# PowerB.net
KiCad netlist of a schematic drawn in Altium Designer
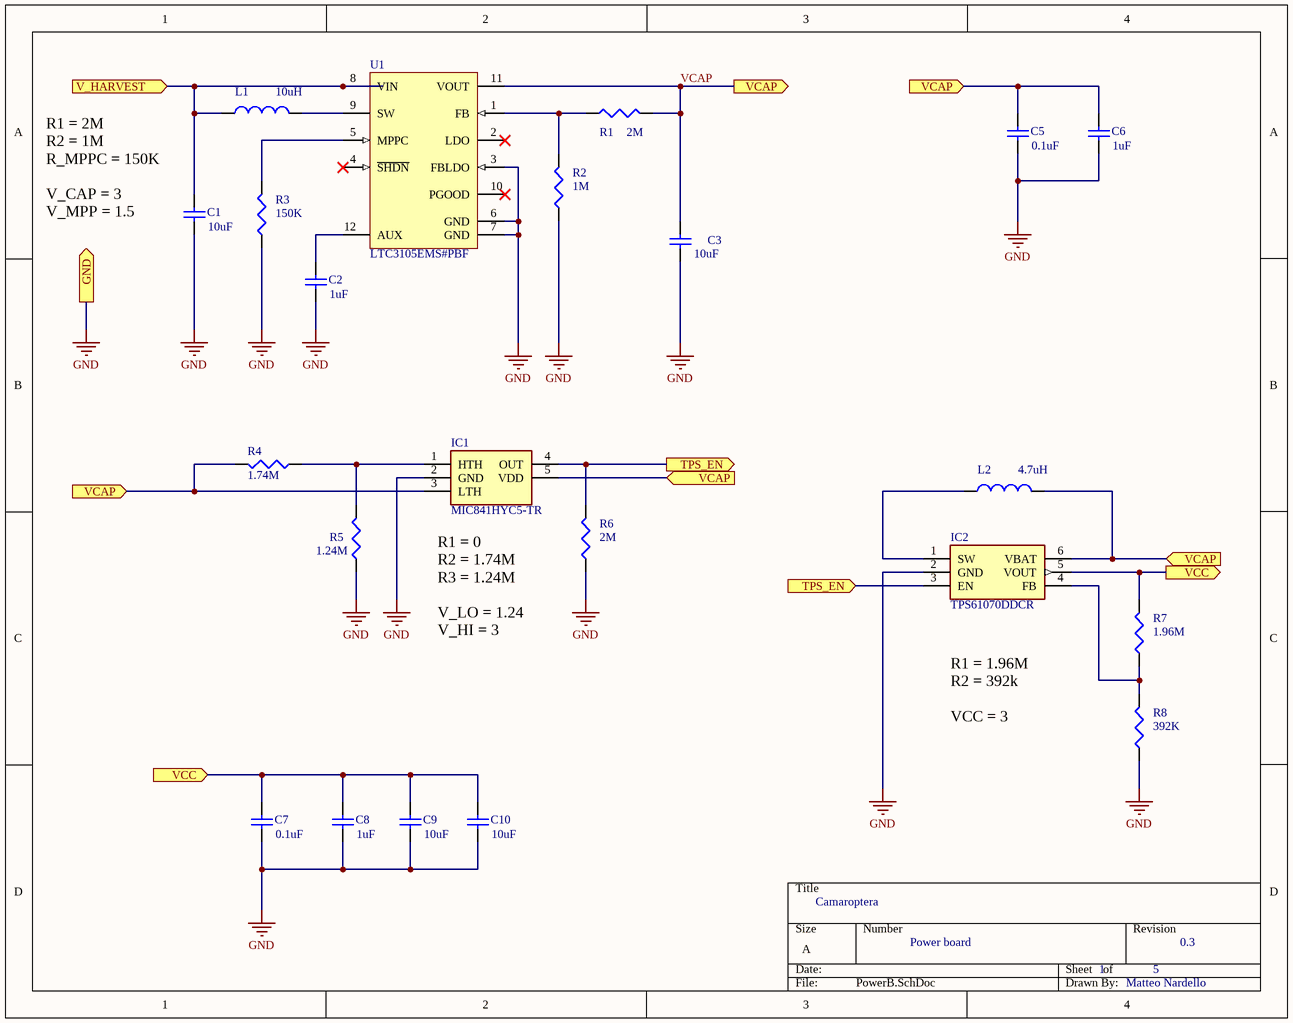
[diagram p0: PowerB.SchDoc]

(export (version "E")
  (design (tool "Eeschema 10.0.6"))
  (components
    (comp (ref "C1")
      (value "10uF")
      (footprint "1608[0603]")
      (description "CAP CER 6.3V X5R/X7R 0603")
      (fields (field (name "Comment") "Cap") (field (name "PUBLISHER") "Altium Limited"))
      (libsource (lib "Miscellaneous Devices") (part "Cap"))
    )
    (comp (ref "C2")
      (value "1uF")
      (footprint "1608[0603]")
      (description "CAP CER 6.3V X5R/X7R 0603")
      (fields (field (name "Comment") "Cap") (field (name "PUBLISHER") "Altium Limited"))
      (libsource (lib "Miscellaneous Devices") (part "Cap"))
    )
    (comp (ref "C3")
      (value "10uF")
      (footprint "1608[0603]")
      (description "CAP CER 6.3V X5R/X7R 0603")
      (fields (field (name "Comment") "Cap") (field (name "PUBLISHER") "Altium Limited"))
      (libsource (lib "Miscellaneous Devices") (part "Cap"))
    )
    (comp (ref "C5")
      (value "0.1uF")
      (footprint "1608[0603]")
      (description "CAP CER 6.3V X5R/X7R 0603")
      (fields (field (name "Comment") "Cap") (field (name "PUBLISHER") "Altium Limited"))
      (libsource (lib "Miscellaneous Devices") (part "Cap"))
    )
    (comp (ref "C6")
      (value "1uF")
      (footprint "1608[0603]")
      (description "CAP CER 6.3V X5R/X7R 0603")
      (fields (field (name "Comment") "Cap") (field (name "PUBLISHER") "Altium Limited"))
      (libsource (lib "Miscellaneous Devices") (part "Cap"))
    )
    (comp (ref "C7")
      (value "0.1uF")
      (footprint "1608[0603]")
      (description "CAP CER 6.3V X5R/X7R 0603")
      (fields (field (name "Comment") "Cap") (field (name "PUBLISHER") "Altium Limited"))
      (libsource (lib "Miscellaneous Devices") (part "Cap"))
    )
    (comp (ref "C8")
      (value "1uF")
      (footprint "1608[0603]")
      (description "CAP CER 6.3V X5R/X7R 0603")
      (fields (field (name "Comment") "Cap") (field (name "PUBLISHER") "Altium Limited"))
      (libsource (lib "Miscellaneous Devices") (part "Cap"))
    )
    (comp (ref "C9")
      (value "10uF")
      (footprint "1608[0603]")
      (description "CAP CER 6.3V X5R/X7R 0603")
      (fields (field (name "Comment") "Cap") (field (name "PUBLISHER") "Altium Limited"))
      (libsource (lib "Miscellaneous Devices") (part "Cap"))
    )
    (comp (ref "C10")
      (value "10uF")
      (footprint "1608[0603]")
      (description "CAP CER 6.3V X5R/X7R 0603")
      (fields (field (name "Comment") "Cap") (field (name "PUBLISHER") "Altium Limited"))
      (libsource (lib "Miscellaneous Devices") (part "Cap"))
    )
    (comp (ref "IC1")
      (value "MIC841HYC5-TR")
      (footprint "SamacSys:SOT65P210X110-5N")
      (description "Comparator with 1.25% Reference and Adjustable Hysteresis")
      (fields
        (field (name "MOUSER PART NUMBER") "998-MIC841HYC5TR")
        (field (name "RS PART NUMBER") "1654292")
      )
      (libsource (lib "*") (part "MIC841HYC5-TR"))
    )
    (comp (ref "IC2")
      (value "TPS61070DDCR")
      (footprint "SamacSys:SOT95P280X110-6N")
      (description "90% Efficient Synchronous Boost Converter With 600-mA Switch")
      (fields (field (name "MOUSER PART NUMBER") "595-TPS61070DDCR"))
      (libsource (lib "*") (part "TPS61070DDCR"))
    )
    (comp (ref "L1")
      (value "10uH")
      (footprint "C1210")
      (description "Inductor")
      (fields (field (name "PART") "CBC3225T100KR") (field (name "PUBLISHER") "Altium Limited"))
      (libsource (lib "Miscellaneous Devices") (part "Inductor"))
    )
    (comp (ref "L2")
      (value "4.7uH")
      (footprint "C1210")
      (description "Inductor")
      (fields (field (name "PART") "CBC3225T4R7MR") (field (name "PUBLISHER") "Altium Limited"))
      (libsource (lib "Miscellaneous Devices") (part "Inductor"))
    )
    (comp (ref "R1")
      (value "2M")
      (footprint "1608[0603]")
      (description "RES 1/10W 1% 0603 SMD")
      (fields (field (name "Comment") "Res3") (field (name "PUBLISHER") "Altium Limited"))
      (libsource (lib "Miscellaneous Devices") (part "Res3"))
    )
    (comp (ref "R2")
      (value "1M")
      (footprint "1608[0603]")
      (description "RES 1/10W 1% 0603 SMD")
      (fields (field (name "Comment") "Res3") (field (name "PUBLISHER") "Altium Limited"))
      (libsource (lib "Miscellaneous Devices") (part "Res3"))
    )
    (comp (ref "R3")
      (value "150K")
      (footprint "1608[0603]")
      (description "RES 1/10W 1% 0603 SMD")
      (fields (field (name "Comment") "Res3") (field (name "PUBLISHER") "Altium Limited"))
      (libsource (lib "Miscellaneous Devices") (part "Res3"))
    )
    (comp (ref "R4")
      (value "1.74M")
      (footprint "1608[0603]")
      (description "RES 1/10W 1% 0603 SMD")
      (fields (field (name "Comment") "Res3") (field (name "PUBLISHER") "Altium Limited"))
      (libsource (lib "Miscellaneous Devices") (part "Res3"))
    )
    (comp (ref "R5")
      (value "1.24M")
      (footprint "1608[0603]")
      (description "RES 1/10W 1% 0603 SMD")
      (fields (field (name "Comment") "Res3") (field (name "PUBLISHER") "Altium Limited"))
      (libsource (lib "Miscellaneous Devices") (part "Res3"))
    )
    (comp (ref "R6")
      (value "2M")
      (footprint "1608[0603]")
      (description "RES 1/10W 1% 0603 SMD")
      (fields (field (name "Comment") "Res3") (field (name "PUBLISHER") "Altium Limited"))
      (libsource (lib "Miscellaneous Devices") (part "Res3"))
    )
    (comp (ref "R7")
      (value "1.96M")
      (footprint "1608[0603]")
      (description "RES 1/10W 1% 0603 SMD")
      (fields (field (name "Comment") "Res3") (field (name "PUBLISHER") "Altium Limited"))
      (libsource (lib "Miscellaneous Devices") (part "Res3"))
    )
    (comp (ref "R8")
      (value "392K")
      (footprint "1608[0603]")
      (description "RES 1/10W 1% 0603 SMD")
      (fields (field (name "Comment") "Res3") (field (name "PUBLISHER") "Altium Limited"))
      (libsource (lib "Miscellaneous Devices") (part "Res3"))
    )
    (comp (ref "U1")
      (value "LTC3105EMS#PBF")
      (footprint "LT-MS-12_N")
      (fields (field (name "MANUFACTURER") "Linear Technology"))
      (libsource (lib "Altium Content Vault") (part "LT-LTC3105-MS-12"))
    )
  )
  (nets
    (net (code "1") (name "/TPS_EN") (class "Default")
      (node (ref "IC1") (pin "4") (pinfunction "OUT_4") (pintype "passive"))
      (node (ref "IC2") (pin "3") (pinfunction "EN_3") (pintype "passive"))
      (node (ref "R6") (pin "2") (pinfunction "2_2") (pintype "passive"))
    )
    (net (code "2") (name "/VCAP") (class "Default")
      (node (ref "C3") (pin "2") (pinfunction "2_2") (pintype "passive"))
      (node (ref "C5") (pin "2") (pinfunction "2_2") (pintype "passive"))
      (node (ref "C6") (pin "2") (pinfunction "2_2") (pintype "passive"))
      (node (ref "IC1") (pin "3") (pinfunction "LTH_3") (pintype "passive"))
      (node (ref "IC1") (pin "5") (pinfunction "VDD_5") (pintype "passive"))
      (node (ref "IC2") (pin "6") (pinfunction "VBAT_6") (pintype "passive"))
      (node (ref "L2") (pin "2") (pinfunction "2_2") (pintype "passive"))
      (node (ref "R1") (pin "2") (pinfunction "2_2") (pintype "passive"))
      (node (ref "R4") (pin "2") (pinfunction "2_2") (pintype "passive"))
      (node (ref "U1") (pin "11") (pinfunction "VOUT_11") (pintype "power_in"))
    )
    (net (code "3") (name "/VCC") (class "Default")
      (node (ref "C10") (pin "2") (pinfunction "2_2") (pintype "passive"))
      (node (ref "C7") (pin "2") (pinfunction "2_2") (pintype "passive"))
      (node (ref "C8") (pin "2") (pinfunction "2_2") (pintype "passive"))
      (node (ref "C9") (pin "2") (pinfunction "2_2") (pintype "passive"))
      (node (ref "IC2") (pin "5") (pinfunction "VOUT_5") (pintype "output"))
      (node (ref "R7") (pin "2") (pinfunction "2_2") (pintype "passive"))
    )
    (net (code "4") (name "/V_HARVEST") (class "Default")
      (node (ref "C1") (pin "2") (pinfunction "2_2") (pintype "passive"))
      (node (ref "L1") (pin "1") (pinfunction "1_1") (pintype "passive"))
      (node (ref "U1") (pin "8") (pinfunction "VIN_8") (pintype "power_in"))
    )
    (net (code "5") (name "GND") (class "Default")
      (node (ref "C1") (pin "1") (pinfunction "1_1") (pintype "passive"))
      (node (ref "C10") (pin "1") (pinfunction "1_1") (pintype "passive"))
      (node (ref "C2") (pin "1") (pinfunction "1_1") (pintype "passive"))
      (node (ref "C3") (pin "1") (pinfunction "1_1") (pintype "passive"))
      (node (ref "C5") (pin "1") (pinfunction "1_1") (pintype "passive"))
      (node (ref "C6") (pin "1") (pinfunction "1_1") (pintype "passive"))
      (node (ref "C7") (pin "1") (pinfunction "1_1") (pintype "passive"))
      (node (ref "C8") (pin "1") (pinfunction "1_1") (pintype "passive"))
      (node (ref "C9") (pin "1") (pinfunction "1_1") (pintype "passive"))
      (node (ref "IC1") (pin "2") (pinfunction "GND_2") (pintype "passive"))
      (node (ref "IC2") (pin "2") (pinfunction "GND_2") (pintype "power_in"))
      (node (ref "R2") (pin "1") (pinfunction "1_1") (pintype "passive"))
      (node (ref "R3") (pin "1") (pinfunction "1_1") (pintype "passive"))
      (node (ref "R5") (pin "1") (pinfunction "1_1") (pintype "passive"))
      (node (ref "R6") (pin "1") (pinfunction "1_1") (pintype "passive"))
      (node (ref "R8") (pin "1") (pinfunction "1_1") (pintype "passive"))
      (node (ref "U1") (pin "3") (pinfunction "FBLDO_3") (pintype "input"))
      (node (ref "U1") (pin "6") (pinfunction "GND_6") (pintype "power_in"))
      (node (ref "U1") (pin "7") (pinfunction "GND_7") (pintype "power_in"))
    )
    (net (code "6") (name "Net-(IC1-HTH)") (class "Default")
      (node (ref "IC1") (pin "1") (pinfunction "HTH_1") (pintype "passive"))
      (node (ref "R4") (pin "1") (pinfunction "1_1") (pintype "passive"))
      (node (ref "R5") (pin "2") (pinfunction "2_2") (pintype "passive"))
    )
    (net (code "7") (name "Net-(IC2-FB)") (class "Default")
      (node (ref "IC2") (pin "4") (pinfunction "FB_4") (pintype "passive"))
      (node (ref "R7") (pin "1") (pinfunction "1_1") (pintype "passive"))
      (node (ref "R8") (pin "2") (pinfunction "2_2") (pintype "passive"))
    )
    (net (code "8") (name "Net-(IC2-SW)") (class "Default")
      (node (ref "IC2") (pin "1") (pinfunction "SW_1") (pintype "passive"))
      (node (ref "L2") (pin "1") (pinfunction "1_1") (pintype "passive"))
    )
    (net (code "9") (name "Net-(U1-AUX)") (class "Default")
      (node (ref "C2") (pin "2") (pinfunction "2_2") (pintype "passive"))
      (node (ref "U1") (pin "12") (pinfunction "AUX_12") (pintype "power_in"))
    )
    (net (code "10") (name "Net-(U1-FB)") (class "Default")
      (node (ref "R1") (pin "1") (pinfunction "1_1") (pintype "passive"))
      (node (ref "R2") (pin "2") (pinfunction "2_2") (pintype "passive"))
      (node (ref "U1") (pin "1") (pinfunction "FB_1") (pintype "input"))
    )
    (net (code "11") (name "Net-(U1-MPPC)") (class "Default")
      (node (ref "R3") (pin "2") (pinfunction "2_2") (pintype "passive"))
      (node (ref "U1") (pin "5") (pinfunction "MPPC_5") (pintype "input"))
    )
    (net (code "12") (name "Net-(U1-SW)") (class "Default")
      (node (ref "L1") (pin "2") (pinfunction "2_2") (pintype "passive"))
      (node (ref "U1") (pin "9") (pinfunction "SW_9") (pintype "power_in"))
    )
    (net (code "13") (name "unconnected-(U1-LDO-Pad2)") (class "Default")
      (node (ref "U1") (pin "2") (pinfunction "LDO_2") (pintype "power_in+no_connect"))
    )
    (net (code "14") (name "unconnected-(U1-PGOOD-Pad10)") (class "Default")
      (node (ref "U1") (pin "10") (pinfunction "PGOOD_10") (pintype "open_collector+no_connect"))
    )
    (net (code "15") (name "unconnected-(U1-~{SHDN}-Pad4)") (class "Default")
      (node (ref "U1") (pin "4") (pinfunction "~{SHDN}_4") (pintype "input+no_connect"))
    )
  )
)
